# FMBTECH.net
KiCad netlist of a schematic drawn in EAGLE
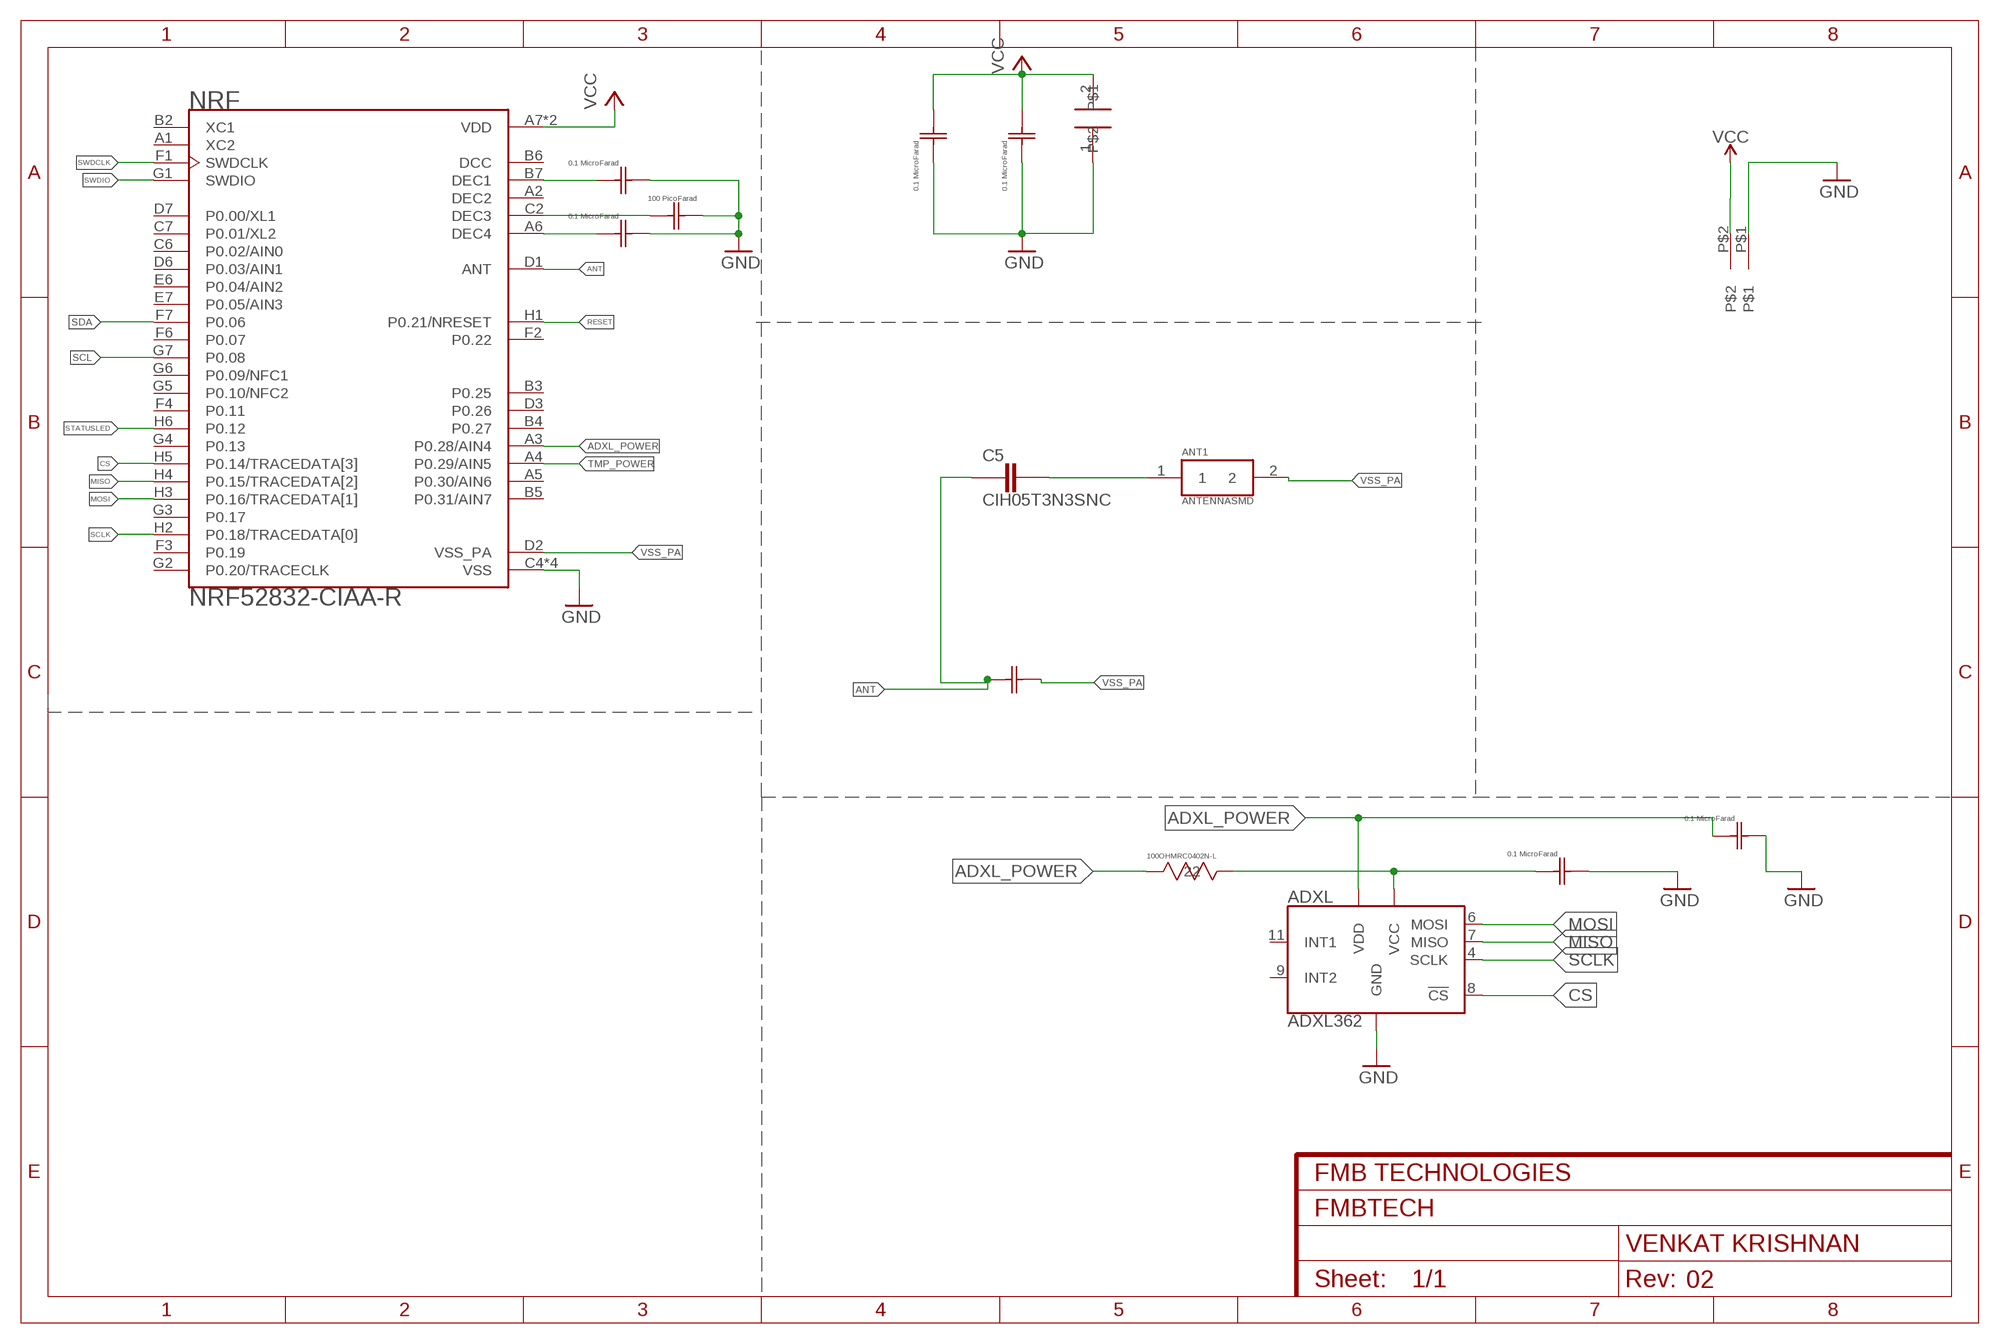
[diagram p0: schematic, sheet 1]

(export (version "E")
  (design (tool "Eeschema 10.0.6"))
  (components
    (comp (ref "ADXL")
      (value "ADXL362")
      (footprint "eagle-import:TFLGA-16_3.3MMX3.1MM")
      (fields (field (name "MF") "Analog Devices") (field (name "MP") "ADXL362BCCZ-RL7"))
      (libsource (lib "eagle-import") (part "ADXL362"))
    )
    (comp (ref "ANT1")
      (value "ANTENNASMD")
      (footprint "eagle-import:1")
      (fields (field (name "MF") "Pulse") (field (name "MP") "W3008"))
      (libsource (lib "eagle-import") (part "ANTENNASMD"))
    )
    (comp (ref "C1")
      (value "02016D104KAT2A")
      (footprint "eagle-import:0201")
      (libsource (lib "eagle-import") (part "02016D104KAT2A"))
    )
    (comp (ref "C2")
      (value "02016D104KAT2A")
      (footprint "eagle-import:0201")
      (libsource (lib "eagle-import") (part "02016D104KAT2A"))
    )
    (comp (ref "C3")
      (value "GRM0335C1E101JA01D")
      (footprint "eagle-import:G-033")
      (libsource (lib "eagle-import") (part "GRM0335C1E101JA01D"))
    )
    (comp (ref "C4")
      (value "GJM1555C1H1R0BB01DG-155-L")
      (footprint "eagle-import:G-155-L")
      (fields (field (name "MANUFACTURER_PART_NUMBER") "GJM1555C1H1R0BB01D"))
      (libsource (lib "eagle-import") (part "GJM1555C1H1R0BB01DG-155-L"))
    )
    (comp (ref "C5")
      (value "CIH05T3N3SNC")
      (footprint "eagle-import:CAPC1005X55N")
      (fields (field (name "MF") "Samsung"))
      (libsource (lib "eagle-import") (part "CIH05T3N3SNC"))
    )
    (comp (ref "C6")
      (value "02016D104KAT2A")
      (footprint "eagle-import:0201")
      (libsource (lib "eagle-import") (part "02016D104KAT2A"))
    )
    (comp (ref "C7")
      (value "02016D104KAT2A")
      (footprint "eagle-import:0201")
      (libsource (lib "eagle-import") (part "02016D104KAT2A"))
    )
    (comp (ref "C8")
      (value "02016D104KAT2A")
      (footprint "eagle-import:0201")
      (libsource (lib "eagle-import") (part "02016D104KAT2A"))
    )
    (comp (ref "C9")
      (value "02016D104KAT2A")
      (footprint "eagle-import:0201")
      (libsource (lib "eagle-import") (part "02016D104KAT2A"))
    )
    (comp (ref "NRF")
      (value "NRF52832-CIAA-R")
      (footprint "eagle-import:BGA50N40P7X8_300X320X40")
      (fields (field (name "MF") "Nordic"))
      (libsource (lib "eagle-import") (part "NRF52832-CIAA-R"))
    )
    (comp (ref "R6")
      (value "100OHMRC0402N-L")
      (footprint "eagle-import:RES")
      (fields (field (name "MANUFACTURER_PART_NUMBER") "RC0402FR07100RL"))
      (libsource (lib "eagle-import") (part "100OHMRC0402N-L"))
    )
    (comp (ref "U$1")
      (value "4.7µF")
      (footprint "eagle-import:CAP")
      (libsource (lib "eagle-import") (part "4.7µF"))
    )
    (comp (ref "U$4")
      (value "SUPPLY")
      (footprint "eagle-import:SUPPLY")
      (libsource (lib "eagle-import") (part "SUPPLY"))
    )
  )
  (nets
    (net (code "1") (name "/DCC") (class "Default")
      (node (ref "NRF") (pin "B6") (pinfunction "DCC_B6") (pintype "power_in"))
    )
    (net (code "2") (name "/DEC2") (class "Default")
      (node (ref "NRF") (pin "A2") (pinfunction "DEC2_A2") (pintype "power_in"))
    )
    (net (code "3") (name "ADXL_POWER") (class "Default")
      (node (ref "ADXL") (pin "1") (pinfunction "VDD_1") (pintype "bidirectional"))
      (node (ref "C9") (pin "1") (pinfunction "1_1") (pintype "passive"))
      (node (ref "NRF") (pin "A3") (pinfunction "P0.28/AIN4_A3") (pintype "bidirectional"))
      (node (ref "R6") (pin "1") (pinfunction "11_1") (pintype "passive"))
    )
    (net (code "4") (name "ANT") (class "Default")
      (node (ref "C4") (pin "1") (pinfunction "11_1") (pintype "passive"))
      (node (ref "C5") (pin "1") (pinfunction "1_1") (pintype "passive"))
      (node (ref "NRF") (pin "D1") (pinfunction "ANT_D1") (pintype "passive"))
    )
    (net (code "5") (name "CS") (class "Default")
      (node (ref "ADXL") (pin "8") (pinfunction "~{CS}_8") (pintype "bidirectional"))
      (node (ref "NRF") (pin "H5") (pinfunction "P0.14/TRACEDATA[3]_H5") (pintype "bidirectional"))
    )
    (net (code "6") (name "GND") (class "Default")
      (node (ref "ADXL") (pin "12") (pinfunction "GND_12") (pintype "bidirectional"))
      (node (ref "ADXL") (pin "13") (pinfunction "GND_13") (pintype "bidirectional"))
      (node (ref "ADXL") (pin "16") (pinfunction "GND_16") (pintype "bidirectional"))
      (node (ref "C1") (pin "2") (pinfunction "2_2") (pintype "passive"))
      (node (ref "C2") (pin "2") (pinfunction "2_2") (pintype "passive"))
      (node (ref "C3") (pin "2") (pinfunction "22_2") (pintype "passive"))
      (node (ref "C6") (pin "1") (pinfunction "1_1") (pintype "passive"))
      (node (ref "C7") (pin "1") (pinfunction "1_1") (pintype "passive"))
      (node (ref "C8") (pin "2") (pinfunction "2_2") (pintype "passive"))
      (node (ref "C9") (pin "2") (pinfunction "2_2") (pintype "passive"))
      (node (ref "NRF") (pin "C4") (pinfunction "VSS_C4") (pintype "power_in"))
      (node (ref "NRF") (pin "C5") (pinfunction "VSS_C5") (pintype "power_in"))
      (node (ref "NRF") (pin "E3") (pinfunction "VSS_E3") (pintype "power_in"))
      (node (ref "NRF") (pin "F5") (pinfunction "VSS_F5") (pintype "power_in"))
      (node (ref "U$1") (pin "1") (pinfunction "P$1_1") (pintype "bidirectional"))
      (node (ref "U$4") (pin "P$1") (pinfunction "P$1_P$1") (pintype "bidirectional"))
    )
    (net (code "7") (name "MISO") (class "Default")
      (node (ref "ADXL") (pin "7") (pinfunction "MISO_7") (pintype "bidirectional"))
      (node (ref "NRF") (pin "H4") (pinfunction "P0.15/TRACEDATA[2]_H4") (pintype "bidirectional"))
    )
    (net (code "8") (name "MOSI") (class "Default")
      (node (ref "ADXL") (pin "6") (pinfunction "MOSI_6") (pintype "bidirectional"))
      (node (ref "NRF") (pin "H3") (pinfunction "P0.16/TRACEDATA[1]_H3") (pintype "bidirectional"))
    )
    (net (code "9") (name "Net-(ADXL-VCC)") (class "Default")
      (node (ref "ADXL") (pin "14") (pinfunction "VCC_14") (pintype "bidirectional"))
      (node (ref "C8") (pin "1") (pinfunction "1_1") (pintype "passive"))
      (node (ref "R6") (pin "2") (pinfunction "22_2") (pintype "passive"))
    )
    (net (code "10") (name "Net-(ANT1-Pad1)") (class "Default")
      (node (ref "ANT1") (pin "1") (pinfunction "1_1") (pintype "passive"))
      (node (ref "C5") (pin "2") (pinfunction "2_2") (pintype "passive"))
    )
    (net (code "11") (name "Net-(C3-11)") (class "Default")
      (node (ref "C3") (pin "1") (pinfunction "11_1") (pintype "passive"))
      (node (ref "NRF") (pin "C2") (pinfunction "DEC3_C2") (pintype "power_in"))
    )
    (net (code "12") (name "Net-(NRF-DEC1)") (class "Default")
      (node (ref "C1") (pin "1") (pinfunction "1_1") (pintype "passive"))
      (node (ref "NRF") (pin "B7") (pinfunction "DEC1_B7") (pintype "power_in"))
    )
    (net (code "13") (name "Net-(NRF-DEC4)") (class "Default")
      (node (ref "C2") (pin "1") (pinfunction "1_1") (pintype "passive"))
      (node (ref "NRF") (pin "A6") (pinfunction "DEC4_A6") (pintype "power_in"))
    )
    (net (code "14") (name "RESET") (class "Default")
      (node (ref "NRF") (pin "H1") (pinfunction "P0.21/NRESET_H1") (pintype "bidirectional"))
    )
    (net (code "15") (name "SCL") (class "Default")
      (node (ref "NRF") (pin "G7") (pinfunction "P0.08_G7") (pintype "bidirectional"))
    )
    (net (code "16") (name "SCLK") (class "Default")
      (node (ref "ADXL") (pin "4") (pinfunction "SCLK_4") (pintype "bidirectional"))
      (node (ref "NRF") (pin "H2") (pinfunction "P0.18/TRACEDATA[0]_H2") (pintype "bidirectional"))
    )
    (net (code "17") (name "SDA") (class "Default")
      (node (ref "NRF") (pin "F7") (pinfunction "P0.06_F7") (pintype "bidirectional"))
    )
    (net (code "18") (name "STATUSLED") (class "Default")
      (node (ref "NRF") (pin "H6") (pinfunction "P0.12_H6") (pintype "bidirectional"))
    )
    (net (code "19") (name "SWDCLK") (class "Default")
      (node (ref "NRF") (pin "F1") (pinfunction "SWDCLK_F1") (pintype "input"))
    )
    (net (code "20") (name "SWDIO") (class "Default")
      (node (ref "NRF") (pin "G1") (pinfunction "SWDIO_G1") (pintype "bidirectional"))
    )
    (net (code "21") (name "TMP_POWER") (class "Default")
      (node (ref "NRF") (pin "A4") (pinfunction "P0.29/AIN5_A4") (pintype "bidirectional"))
    )
    (net (code "22") (name "VCC") (class "Default")
      (node (ref "C6") (pin "2") (pinfunction "2_2") (pintype "passive"))
      (node (ref "C7") (pin "2") (pinfunction "2_2") (pintype "passive"))
      (node (ref "NRF") (pin "A7") (pinfunction "VDD_A7") (pintype "power_in"))
      (node (ref "NRF") (pin "H7") (pinfunction "VDD_H7") (pintype "power_in"))
      (node (ref "U$1") (pin "2") (pinfunction "P$2_2") (pintype "bidirectional"))
      (node (ref "U$4") (pin "P$2") (pinfunction "P$2_P$2") (pintype "bidirectional"))
    )
    (net (code "23") (name "VSS_PA") (class "Default")
      (node (ref "ANT1") (pin "2") (pinfunction "2_2") (pintype "passive"))
      (node (ref "C4") (pin "2") (pinfunction "22_2") (pintype "passive"))
      (node (ref "NRF") (pin "D2") (pinfunction "VSS_PA_D2") (pintype "power_in"))
    )
    (net (code "24") (name "unconnected-(ADXL-INT1-Pad11)") (class "Default")
      (node (ref "ADXL") (pin "11") (pinfunction "INT1_11") (pintype "bidirectional"))
    )
    (net (code "25") (name "unconnected-(ADXL-INT2-Pad9)") (class "Default")
      (node (ref "ADXL") (pin "9") (pinfunction "INT2_9") (pintype "bidirectional"))
    )
    (net (code "26") (name "unconnected-(NRF-P0.00{slash}XL1-PadD7)") (class "Default")
      (node (ref "NRF") (pin "D7") (pinfunction "P0.00/XL1_D7") (pintype "bidirectional"))
    )
    (net (code "27") (name "unconnected-(NRF-P0.01{slash}XL2-PadC7)") (class "Default")
      (node (ref "NRF") (pin "C7") (pinfunction "P0.01/XL2_C7") (pintype "bidirectional"))
    )
    (net (code "28") (name "unconnected-(NRF-P0.02{slash}AIN0-PadC6)") (class "Default")
      (node (ref "NRF") (pin "C6") (pinfunction "P0.02/AIN0_C6") (pintype "bidirectional"))
    )
    (net (code "29") (name "unconnected-(NRF-P0.03{slash}AIN1-PadD6)") (class "Default")
      (node (ref "NRF") (pin "D6") (pinfunction "P0.03/AIN1_D6") (pintype "bidirectional"))
    )
    (net (code "30") (name "unconnected-(NRF-P0.04{slash}AIN2-PadE6)") (class "Default")
      (node (ref "NRF") (pin "E6") (pinfunction "P0.04/AIN2_E6") (pintype "bidirectional"))
    )
    (net (code "31") (name "unconnected-(NRF-P0.05{slash}AIN3-PadE7)") (class "Default")
      (node (ref "NRF") (pin "E7") (pinfunction "P0.05/AIN3_E7") (pintype "bidirectional"))
    )
    (net (code "32") (name "unconnected-(NRF-P0.07-PadF6)") (class "Default")
      (node (ref "NRF") (pin "F6") (pinfunction "P0.07_F6") (pintype "bidirectional"))
    )
    (net (code "33") (name "unconnected-(NRF-P0.09{slash}NFC1-PadG6)") (class "Default")
      (node (ref "NRF") (pin "G6") (pinfunction "P0.09/NFC1_G6") (pintype "bidirectional"))
    )
    (net (code "34") (name "unconnected-(NRF-P0.10{slash}NFC2-PadG5)") (class "Default")
      (node (ref "NRF") (pin "G5") (pinfunction "P0.10/NFC2_G5") (pintype "bidirectional"))
    )
    (net (code "35") (name "unconnected-(NRF-P0.11-PadF4)") (class "Default")
      (node (ref "NRF") (pin "F4") (pinfunction "P0.11_F4") (pintype "bidirectional"))
    )
    (net (code "36") (name "unconnected-(NRF-P0.13-PadG4)") (class "Default")
      (node (ref "NRF") (pin "G4") (pinfunction "P0.13_G4") (pintype "bidirectional"))
    )
    (net (code "37") (name "unconnected-(NRF-P0.17-PadG3)") (class "Default")
      (node (ref "NRF") (pin "G3") (pinfunction "P0.17_G3") (pintype "bidirectional"))
    )
    (net (code "38") (name "unconnected-(NRF-P0.19-PadF3)") (class "Default")
      (node (ref "NRF") (pin "F3") (pinfunction "P0.19_F3") (pintype "bidirectional"))
    )
    (net (code "39") (name "unconnected-(NRF-P0.20{slash}TRACECLK-PadG2)") (class "Default")
      (node (ref "NRF") (pin "G2") (pinfunction "P0.20/TRACECLK_G2") (pintype "bidirectional"))
    )
    (net (code "40") (name "unconnected-(NRF-P0.22-PadF2)") (class "Default")
      (node (ref "NRF") (pin "F2") (pinfunction "P0.22_F2") (pintype "bidirectional"))
    )
    (net (code "41") (name "unconnected-(NRF-P0.25-PadB3)") (class "Default")
      (node (ref "NRF") (pin "B3") (pinfunction "P0.25_B3") (pintype "bidirectional"))
    )
    (net (code "42") (name "unconnected-(NRF-P0.26-PadD3)") (class "Default")
      (node (ref "NRF") (pin "D3") (pinfunction "P0.26_D3") (pintype "bidirectional"))
    )
    (net (code "43") (name "unconnected-(NRF-P0.27-PadB4)") (class "Default")
      (node (ref "NRF") (pin "B4") (pinfunction "P0.27_B4") (pintype "bidirectional"))
    )
    (net (code "44") (name "unconnected-(NRF-P0.30{slash}AIN6-PadA5)") (class "Default")
      (node (ref "NRF") (pin "A5") (pinfunction "P0.30/AIN6_A5") (pintype "bidirectional"))
    )
    (net (code "45") (name "unconnected-(NRF-P0.31{slash}AIN7-PadB5)") (class "Default")
      (node (ref "NRF") (pin "B5") (pinfunction "P0.31/AIN7_B5") (pintype "bidirectional"))
    )
    (net (code "46") (name "unconnected-(NRF-XC1-PadB2)") (class "Default")
      (node (ref "NRF") (pin "B2") (pinfunction "XC1_B2") (pintype "input"))
    )
    (net (code "47") (name "unconnected-(NRF-XC2-PadA1)") (class "Default")
      (node (ref "NRF") (pin "A1") (pinfunction "XC2_A1") (pintype "input"))
    )
  )
)
